# lock_in.net
KiCad netlist of a schematic drawn in Altium Designer
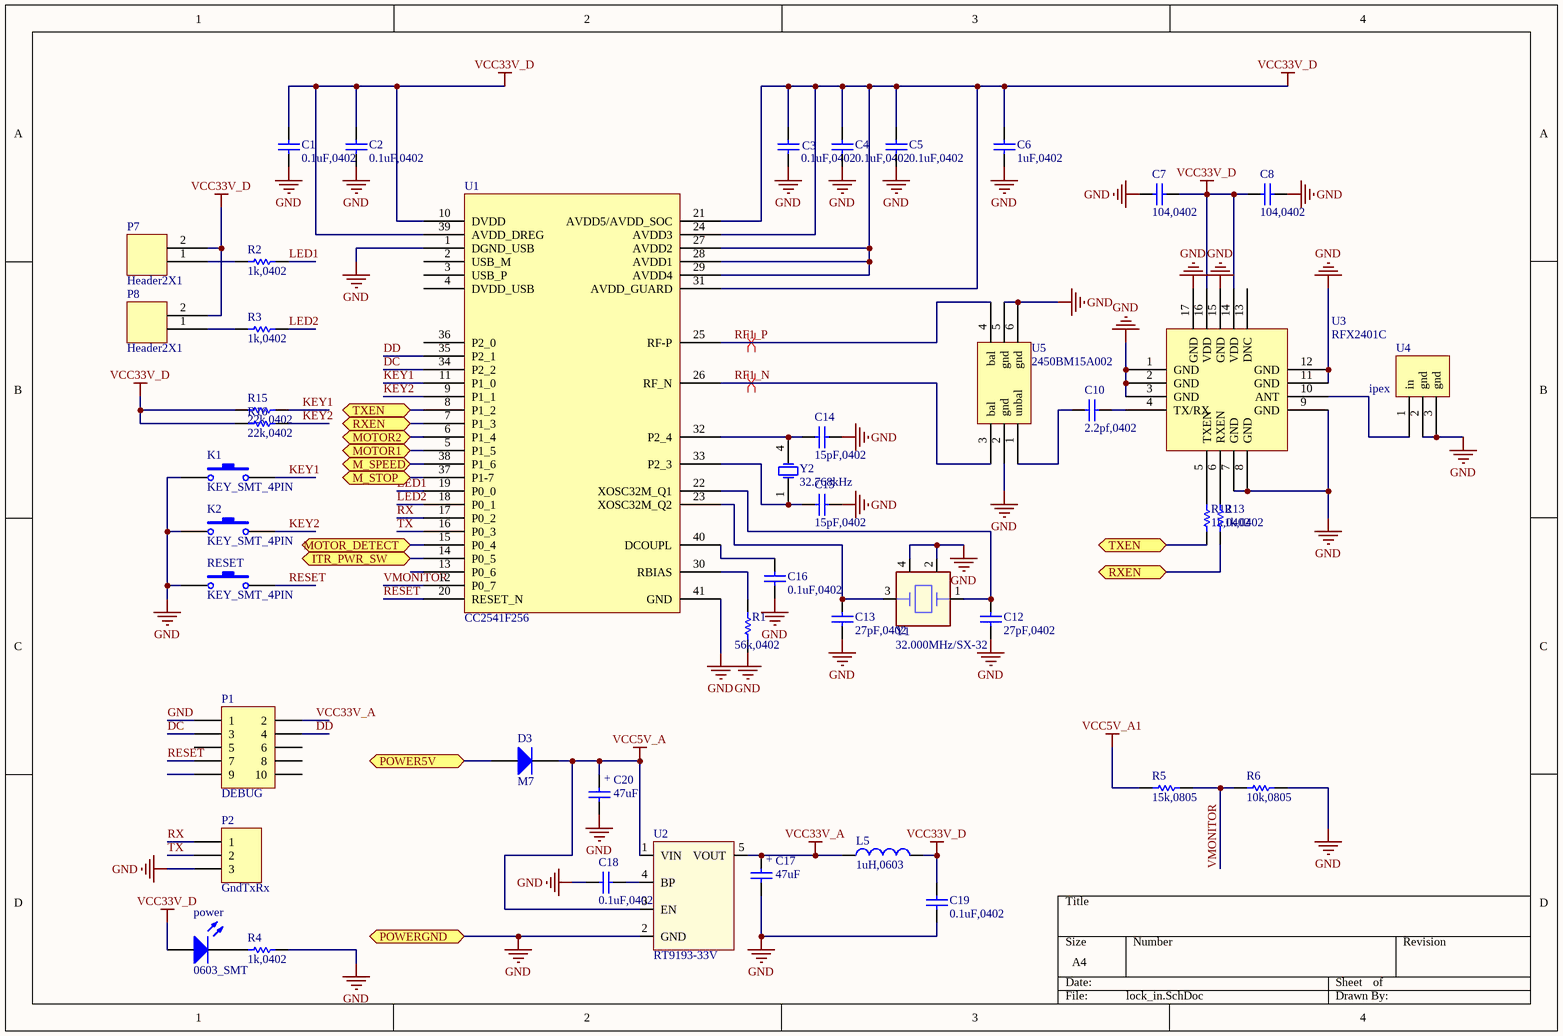
[diagram p0: lock_in.SchDoc]

(export (version "E")
  (design (tool "Eeschema 10.0.6"))
  (components
    (comp (ref "C1")
      (value "0.1uF,0402")
      (footprint "C0402")
      (description "Capacitor")
      (fields (field (name "PUBLISHER") "Altium Limited"))
      (libsource (lib "Inte") (part "CAP"))
    )
    (comp (ref "C2")
      (value "0.1uF,0402")
      (footprint "C0402")
      (description "Capacitor")
      (fields (field (name "PUBLISHER") "Altium Limited"))
      (libsource (lib "Inte") (part "CAP"))
    )
    (comp (ref "C3")
      (value "0.1uF,0402")
      (footprint "C0402")
      (description "Capacitor")
      (fields (field (name "PUBLISHER") "Altium Limited"))
      (libsource (lib "Inte") (part "CAP"))
    )
    (comp (ref "C4")
      (value "0.1uF,0402")
      (footprint "C0402")
      (description "Capacitor")
      (fields (field (name "PUBLISHER") "Altium Limited"))
      (libsource (lib "Inte") (part "CAP"))
    )
    (comp (ref "C5")
      (value "0.1uF,0402")
      (footprint "C0402")
      (description "Capacitor")
      (fields (field (name "PUBLISHER") "Altium Limited"))
      (libsource (lib "Inte") (part "CAP"))
    )
    (comp (ref "C6")
      (value "1uF,0402")
      (footprint "C0402")
      (description "Capacitor")
      (fields (field (name "PUBLISHER") "Altium Limited"))
      (libsource (lib "Inte") (part "CAP"))
    )
    (comp (ref "C7")
      (value "104,0402")
      (footprint "C0402")
      (description "Capacitor")
      (fields (field (name "PUBLISHER") "Altium Limited"))
      (libsource (lib "Inte") (part "CAP"))
    )
    (comp (ref "C8")
      (value "104,0402")
      (footprint "C0402")
      (description "Capacitor")
      (fields (field (name "PUBLISHER") "Altium Limited"))
      (libsource (lib "Inte") (part "CAP"))
    )
    (comp (ref "C10")
      (value "2.2pf,0402")
      (footprint "C0402")
      (description "Capacitor")
      (fields (field (name "PUBLISHER") "Altium Limited"))
      (libsource (lib "Inte") (part "CAP"))
    )
    (comp (ref "C12")
      (value "27pF,0402")
      (footprint "C0402")
      (description "Capacitor")
      (fields (field (name "PUBLISHER") "Altium Limited"))
      (libsource (lib "Inte") (part "CAP"))
    )
    (comp (ref "C13")
      (value "27pF,0402")
      (footprint "C0402")
      (description "Capacitor")
      (fields (field (name "PUBLISHER") "Altium Limited"))
      (libsource (lib "Inte") (part "CAP"))
    )
    (comp (ref "C14")
      (value "15pF,0402")
      (footprint "C0402")
      (description "Capacitor")
      (fields (field (name "PUBLISHER") "Altium Limited"))
      (libsource (lib "Inte") (part "CAP"))
    )
    (comp (ref "C15")
      (value "15pF,0402")
      (footprint "C0402")
      (description "Capacitor")
      (fields (field (name "PUBLISHER") "Altium Limited"))
      (libsource (lib "Inte") (part "CAP"))
    )
    (comp (ref "C16")
      (value "0.1uF,0402")
      (footprint "C0402")
      (description "Capacitor")
      (fields (field (name "PUBLISHER") "Altium Limited"))
      (libsource (lib "Inte") (part "CAP"))
    )
    (comp (ref "C17")
      (value "47uF")
      (footprint "3216")
      (description "tantalum capacitor")
      (libsource (lib "Inte") (part "E_CAP"))
    )
    (comp (ref "C18")
      (value "0.1uF,0402")
      (footprint "C0402")
      (description "Capacitor")
      (fields (field (name "PUBLISHER") "Altium Limited"))
      (libsource (lib "Inte") (part "CAP"))
    )
    (comp (ref "C19")
      (value "0.1uF,0402")
      (footprint "C0402")
      (description "Capacitor")
      (fields (field (name "PUBLISHER") "Altium Limited"))
      (libsource (lib "Inte") (part "CAP"))
    )
    (comp (ref "C20")
      (value "47uF")
      (footprint "3216")
      (description "tantalum capacitor")
      (libsource (lib "Inte") (part "E_CAP"))
    )
    (comp (ref "D3")
      (value "M7")
      (footprint "DO214AC")
      (description "diode")
      (libsource (lib "Inte") (part "DIODE"))
    )
    (comp (ref "K1")
      (value "KEY_SMT_4PIN")
      (footprint "KEY-SMT")
      (description "key")
      (libsource (lib "Inte") (part "KEY"))
    )
    (comp (ref "K2")
      (value "KEY_SMT_4PIN")
      (footprint "KEY-SMT")
      (description "key")
      (libsource (lib "Inte") (part "KEY"))
    )
    (comp (ref "L5")
      (value "1uH,0603")
      (footprint "L0603")
      (description "Inductor")
      (fields (field (name "PUBLISHER") "Altium Limited"))
      (libsource (lib "Inte") (part "Inductor"))
    )
    (comp (ref "P1")
      (value "DEBUG")
      (footprint "HDR2X5")
      (description "Header, 5-Pin, Dual row")
      (fields (field (name "PUBLISHER") "Altium Limited"))
      (libsource (lib "Inte") (part "Header 5X2"))
    )
    (comp (ref "P2")
      (value "GndTxRx")
      (footprint "HDR1X3")
      (description "Header, 3-Pin")
      (fields (field (name "PUBLISHER") "Altium Limited"))
      (libsource (lib "Miscellaneous Connectors") (part "Header 3"))
    )
    (comp (ref "P7")
      (value "Header2X1")
      (footprint "HDR2X1")
      (description "Header,2-Pin")
      (libsource (lib "Inte") (part "Header 2X1"))
    )
    (comp (ref "P8")
      (value "Header2X1")
      (footprint "HDR2X1")
      (description "Header,2-Pin")
      (libsource (lib "Inte") (part "Header 2X1"))
    )
    (comp (ref "power")
      (value "0603_SMT")
      (footprint "LED0603")
      (description "led")
      (libsource (lib "Inte") (part "LED"))
    )
    (comp (ref "R1")
      (value "56k,0402")
      (footprint "R0402")
      (description "Resistor")
      (fields (field (name "PUBLISHER") "Altium Limited"))
      (libsource (lib "Inte") (part "Res1"))
    )
    (comp (ref "R2")
      (value "1k,0402")
      (footprint "R0402")
      (description "Resistor")
      (fields (field (name "PUBLISHER") "Altium Limited"))
      (libsource (lib "Inte") (part "Res1"))
    )
    (comp (ref "R3")
      (value "1k,0402")
      (footprint "R0402")
      (description "Resistor")
      (fields (field (name "PUBLISHER") "Altium Limited"))
      (libsource (lib "Inte") (part "Res1"))
    )
    (comp (ref "R4")
      (value "1k,0402")
      (footprint "R0402")
      (description "Resistor")
      (fields (field (name "PUBLISHER") "Altium Limited"))
      (libsource (lib "Inte") (part "Res1"))
    )
    (comp (ref "R5")
      (value "15k,0805")
      (footprint "R0805")
      (description "Resistor")
      (fields (field (name "PUBLISHER") "Altium Limited"))
      (libsource (lib "Inte") (part "Res1"))
    )
    (comp (ref "R6")
      (value "10k,0805")
      (footprint "R0805")
      (description "Resistor")
      (fields (field (name "PUBLISHER") "Altium Limited"))
      (libsource (lib "Inte") (part "Res1"))
    )
    (comp (ref "R12")
      (value "1k,0402")
      (footprint "R0402")
      (description "Resistor")
      (fields (field (name "PUBLISHER") "Altium Limited"))
      (libsource (lib "Inte") (part "Res1"))
    )
    (comp (ref "R13")
      (value "1k,0402")
      (footprint "R0402")
      (description "Resistor")
      (fields (field (name "PUBLISHER") "Altium Limited"))
      (libsource (lib "Inte") (part "Res1"))
    )
    (comp (ref "R15")
      (value "22k,0402")
      (footprint "R0402")
      (description "Resistor")
      (fields (field (name "PUBLISHER") "Altium Limited"))
      (libsource (lib "Inte") (part "Res1"))
    )
    (comp (ref "R16")
      (value "22k,0402")
      (footprint "R0402")
      (description "Resistor")
      (fields (field (name "PUBLISHER") "Altium Limited"))
      (libsource (lib "Inte") (part "Res1"))
    )
    (comp (ref "RESET")
      (value "KEY_SMT_4PIN")
      (footprint "KEY-SMT")
      (description "key")
      (libsource (lib "Inte") (part "KEY"))
    )
    (comp (ref "U1")
      (value "CC2541F256")
      (footprint "PQFP40")
      (description "TI cc2541F256")
      (libsource (lib "Inte") (part "CC254x"))
    )
    (comp (ref "U2")
      (value "RT9193-33V")
      (footprint "SOT-23-5")
      (description "voltage reg")
      (libsource (lib "Inte") (part "RT9193X"))
    )
    (comp (ref "U3") (value "RFX2401C") (footprint "QFN16") (libsource (lib "Inte") (part "RFX2401C")))
    (comp (ref "U4") (value "ipex") (footprint "IPEX") (libsource (lib "Inte") (part "IPEX")))
    (comp (ref "U5")
      (value "2450BM15A002")
      (footprint "2450BM15A002")
      (libsource (lib "Inte") (part "2450BM15A002"))
    )
    (comp (ref "Y1")
      (value "32.000MHz/SX-32")
      (footprint "1210")
      (description "SPXO")
      (libsource (lib "Inte") (part "CRYSTAL_5"))
    )
    (comp (ref "Y2")
      (value "32.768kHz")
      (footprint "1206")
      (description "crystal")
      (libsource (lib "Inte") (part "DA740C"))
    )
  )
  (nets
    (net (code "1") (name "/DC") (class "Default")
      (node (ref "P1") (pin "3") (pinfunction "3_3") (pintype "passive"))
      (node (ref "U1") (pin "34") (pinfunction "P2_2_34") (pintype "passive"))
    )
    (net (code "2") (name "/DD") (class "Default")
      (node (ref "P1") (pin "4") (pinfunction "4_4") (pintype "passive"))
      (node (ref "U1") (pin "35") (pinfunction "P2_1_35") (pintype "passive"))
    )
    (net (code "3") (name "/ITR_PWR_SW") (class "Default")
      (node (ref "U1") (pin "14") (pinfunction "P0_5_14") (pintype "passive"))
    )
    (net (code "4") (name "/KEY1") (class "Default")
      (node (ref "K1") (pin "2") (pinfunction "2_2") (pintype "passive"))
      (node (ref "R15") (pin "2") (pinfunction "2_2") (pintype "passive"))
      (node (ref "U1") (pin "11") (pinfunction "P1_0_11") (pintype "passive"))
    )
    (net (code "5") (name "/KEY2") (class "Default")
      (node (ref "K2") (pin "2") (pinfunction "2_2") (pintype "passive"))
      (node (ref "R16") (pin "2") (pinfunction "2_2") (pintype "passive"))
      (node (ref "U1") (pin "9") (pinfunction "P1_1_9") (pintype "passive"))
    )
    (net (code "6") (name "/LED1") (class "Default")
      (node (ref "R2") (pin "2") (pinfunction "2_2") (pintype "passive"))
      (node (ref "U1") (pin "19") (pinfunction "P0_0_19") (pintype "passive"))
    )
    (net (code "7") (name "/LED2") (class "Default")
      (node (ref "R3") (pin "2") (pinfunction "2_2") (pintype "passive"))
      (node (ref "U1") (pin "18") (pinfunction "P0_1_18") (pintype "passive"))
    )
    (net (code "8") (name "/MOTOR1") (class "Default")
      (node (ref "U1") (pin "5") (pinfunction "P1_5_5") (pintype "passive"))
    )
    (net (code "9") (name "/MOTOR2") (class "Default")
      (node (ref "U1") (pin "6") (pinfunction "P1_4_6") (pintype "passive"))
    )
    (net (code "10") (name "/MOTOR_DETECT") (class "Default")
      (node (ref "U1") (pin "15") (pinfunction "P0_4_15") (pintype "passive"))
    )
    (net (code "11") (name "/M_SPEED") (class "Default")
      (node (ref "U1") (pin "38") (pinfunction "P1_6_38") (pintype "passive"))
    )
    (net (code "12") (name "/M_STOP") (class "Default")
      (node (ref "U1") (pin "37") (pinfunction "P1-7_37") (pintype "passive"))
    )
    (net (code "13") (name "/POWER5V") (class "Default")
      (node (ref "D3") (pin "1") (pinfunction "A_1") (pintype "passive"))
    )
    (net (code "14") (name "/RESET") (class "Default")
      (node (ref "P1") (pin "7") (pinfunction "7_7") (pintype "passive"))
      (node (ref "RESET") (pin "2") (pinfunction "2_2") (pintype "passive"))
      (node (ref "U1") (pin "20") (pinfunction "RESET_N_20") (pintype "passive"))
    )
    (net (code "15") (name "/RF1_N") (class "Default")
      (node (ref "U1") (pin "26") (pinfunction "RF_N_26") (pintype "passive"))
      (node (ref "U5") (pin "3") (pinfunction "bal_3") (pintype "passive"))
    )
    (net (code "16") (name "/RF1_P") (class "Default")
      (node (ref "U1") (pin "25") (pinfunction "RF-P_25") (pintype "passive"))
      (node (ref "U5") (pin "4") (pinfunction "bal_4") (pintype "passive"))
    )
    (net (code "17") (name "/RX") (class "Default")
      (node (ref "P2") (pin "1") (pinfunction "1_1") (pintype "passive"))
      (node (ref "U1") (pin "17") (pinfunction "P0_2_17") (pintype "passive"))
    )
    (net (code "18") (name "/RXEN") (class "Default")
      (node (ref "R13") (pin "1") (pinfunction "1_1") (pintype "passive"))
      (node (ref "U1") (pin "7") (pinfunction "P1_3_7") (pintype "passive"))
    )
    (net (code "19") (name "/TX") (class "Default")
      (node (ref "P2") (pin "2") (pinfunction "2_2") (pintype "passive"))
      (node (ref "U1") (pin "16") (pinfunction "P0_3_16") (pintype "passive"))
    )
    (net (code "20") (name "/TXEN") (class "Default")
      (node (ref "R12") (pin "1") (pinfunction "1_1") (pintype "passive"))
      (node (ref "U1") (pin "8") (pinfunction "P1_2_8") (pintype "passive"))
    )
    (net (code "21") (name "/VMONITOR") (class "Default")
      (node (ref "R5") (pin "2") (pinfunction "2_2") (pintype "passive"))
      (node (ref "R6") (pin "1") (pinfunction "1_1") (pintype "passive"))
      (node (ref "U1") (pin "12") (pinfunction "P0_7_12") (pintype "passive"))
    )
    (net (code "22") (name "GND") (class "Default")
      (node (ref "C1") (pin "1") (pinfunction "1_1") (pintype "passive"))
      (node (ref "C12") (pin "1") (pinfunction "1_1") (pintype "passive"))
      (node (ref "C13") (pin "1") (pinfunction "1_1") (pintype "passive"))
      (node (ref "C14") (pin "2") (pinfunction "2_2") (pintype "passive"))
      (node (ref "C15") (pin "2") (pinfunction "2_2") (pintype "passive"))
      (node (ref "C16") (pin "1") (pinfunction "1_1") (pintype "passive"))
      (node (ref "C17") (pin "2") (pinfunction "2_2") (pintype "passive"))
      (node (ref "C18") (pin "1") (pinfunction "1_1") (pintype "passive"))
      (node (ref "C19") (pin "1") (pinfunction "1_1") (pintype "passive"))
      (node (ref "C2") (pin "1") (pinfunction "1_1") (pintype "passive"))
      (node (ref "C20") (pin "2") (pinfunction "2_2") (pintype "passive"))
      (node (ref "C3") (pin "2") (pinfunction "2_2") (pintype "passive"))
      (node (ref "C4") (pin "1") (pinfunction "1_1") (pintype "passive"))
      (node (ref "C5") (pin "1") (pinfunction "1_1") (pintype "passive"))
      (node (ref "C6") (pin "1") (pinfunction "1_1") (pintype "passive"))
      (node (ref "C7") (pin "1") (pinfunction "1_1") (pintype "passive"))
      (node (ref "C8") (pin "2") (pinfunction "2_2") (pintype "passive"))
      (node (ref "K1") (pin "1") (pinfunction "1_1") (pintype "passive"))
      (node (ref "K2") (pin "1") (pinfunction "1_1") (pintype "passive"))
      (node (ref "P1") (pin "1") (pinfunction "1_1") (pintype "passive"))
      (node (ref "P2") (pin "3") (pinfunction "3_3") (pintype "passive"))
      (node (ref "R1") (pin "1") (pinfunction "1_1") (pintype "passive"))
      (node (ref "R4") (pin "2") (pinfunction "2_2") (pintype "passive"))
      (node (ref "R6") (pin "2") (pinfunction "2_2") (pintype "passive"))
      (node (ref "RESET") (pin "1") (pinfunction "1_1") (pintype "passive"))
      (node (ref "U1") (pin "1") (pinfunction "DGND_USB_1") (pintype "passive"))
      (node (ref "U1") (pin "41") (pinfunction "GND_41") (pintype "passive"))
      (node (ref "U2") (pin "2") (pinfunction "GND_2") (pintype "power_in"))
      (node (ref "U3") (pin "1") (pinfunction "GND_1") (pintype "passive"))
      (node (ref "U3") (pin "11") (pinfunction "GND_11") (pintype "passive"))
      (node (ref "U3") (pin "12") (pinfunction "GND_12") (pintype "passive"))
      (node (ref "U3") (pin "15") (pinfunction "GND_15") (pintype "passive"))
      (node (ref "U3") (pin "17") (pinfunction "GND_17") (pintype "passive"))
      (node (ref "U3") (pin "2") (pinfunction "GND_2") (pintype "passive"))
      (node (ref "U3") (pin "3") (pinfunction "GND_3") (pintype "passive"))
      (node (ref "U3") (pin "7") (pinfunction "GND_7") (pintype "passive"))
      (node (ref "U3") (pin "8") (pinfunction "GND_8") (pintype "passive"))
      (node (ref "U3") (pin "9") (pinfunction "GND_9") (pintype "passive"))
      (node (ref "U4") (pin "2") (pinfunction "gnd_2") (pintype "passive"))
      (node (ref "U4") (pin "3") (pinfunction "gnd_3") (pintype "passive"))
      (node (ref "U5") (pin "2") (pinfunction "gnd_2") (pintype "passive"))
      (node (ref "U5") (pin "5") (pinfunction "gnd_5") (pintype "passive"))
      (node (ref "U5") (pin "6") (pinfunction "gnd_6") (pintype "passive"))
      (node (ref "Y1") (pin "2") (pinfunction "2_2") (pintype "passive"))
      (node (ref "Y1") (pin "4") (pinfunction "4_4") (pintype "passive"))
    )
    (net (code "23") (name "Net-(P7-Pad1)") (class "Default")
      (node (ref "P7") (pin "1") (pinfunction "1_1") (pintype "passive"))
      (node (ref "R2") (pin "1") (pinfunction "1_1") (pintype "passive"))
    )
    (net (code "24") (name "Net-(P8-Pad1)") (class "Default")
      (node (ref "P8") (pin "1") (pinfunction "1_1") (pintype "passive"))
      (node (ref "R3") (pin "1") (pinfunction "1_1") (pintype "passive"))
    )
    (net (code "25") (name "Net-(U1-DCOUPL)") (class "Default")
      (node (ref "C16") (pin "2") (pinfunction "2_2") (pintype "passive"))
      (node (ref "U1") (pin "40") (pinfunction "DCOUPL_40") (pintype "passive"))
    )
    (net (code "26") (name "Net-(U1-P2_3)") (class "Default")
      (node (ref "C15") (pin "1") (pinfunction "1_1") (pintype "passive"))
      (node (ref "U1") (pin "33") (pinfunction "P2_3_33") (pintype "passive"))
      (node (ref "Y2") (pin "1") (pinfunction "OSC1_1") (pintype "passive"))
    )
    (net (code "27") (name "Net-(U1-P2_4)") (class "Default")
      (node (ref "C14") (pin "1") (pinfunction "1_1") (pintype "passive"))
      (node (ref "U1") (pin "32") (pinfunction "P2_4_32") (pintype "passive"))
      (node (ref "Y2") (pin "4") (pinfunction "OSC2_4") (pintype "passive"))
    )
    (net (code "28") (name "Net-(U1-RBIAS)") (class "Default")
      (node (ref "R1") (pin "2") (pinfunction "2_2") (pintype "passive"))
      (node (ref "U1") (pin "30") (pinfunction "RBIAS_30") (pintype "passive"))
    )
    (net (code "29") (name "Net-(U1-XOSC32M_Q1)") (class "Default")
      (node (ref "C12") (pin "2") (pinfunction "2_2") (pintype "passive"))
      (node (ref "U1") (pin "22") (pinfunction "XOSC32M_Q1_22") (pintype "passive"))
      (node (ref "Y1") (pin "1") (pinfunction "1_1") (pintype "passive"))
    )
    (net (code "30") (name "Net-(U1-XOSC32M_Q2)") (class "Default")
      (node (ref "C13") (pin "2") (pinfunction "2_2") (pintype "passive"))
      (node (ref "U1") (pin "23") (pinfunction "XOSC32M_Q2_23") (pintype "passive"))
      (node (ref "Y1") (pin "3") (pinfunction "3_3") (pintype "passive"))
    )
    (net (code "31") (name "Net-(U2-BP)") (class "Default")
      (node (ref "C18") (pin "2") (pinfunction "2_2") (pintype "passive"))
      (node (ref "U2") (pin "4") (pinfunction "BP_4") (pintype "passive"))
    )
    (net (code "32") (name "Net-(U3-ANT)") (class "Default")
      (node (ref "U3") (pin "10") (pinfunction "ANT_10") (pintype "passive"))
      (node (ref "U4") (pin "1") (pinfunction "in_1") (pintype "passive"))
    )
    (net (code "33") (name "Net-(U3-RXEN)") (class "Default")
      (node (ref "R13") (pin "2") (pinfunction "2_2") (pintype "passive"))
      (node (ref "U3") (pin "6") (pinfunction "RXEN_6") (pintype "passive"))
    )
    (net (code "34") (name "Net-(U3-TXEN)") (class "Default")
      (node (ref "R12") (pin "2") (pinfunction "2_2") (pintype "passive"))
      (node (ref "U3") (pin "5") (pinfunction "TXEN_5") (pintype "passive"))
    )
    (net (code "35") (name "Net-(U3-TX{slash}RX)") (class "Default")
      (node (ref "C10") (pin "2") (pinfunction "2_2") (pintype "passive"))
      (node (ref "U3") (pin "4") (pinfunction "TX/RX_4") (pintype "passive"))
    )
    (net (code "36") (name "Net-(U5-unbal)") (class "Default")
      (node (ref "C10") (pin "1") (pinfunction "1_1") (pintype "passive"))
      (node (ref "U5") (pin "1") (pinfunction "unbal_1") (pintype "passive"))
    )
    (net (code "37") (name "Net-(power-K)") (class "Default")
      (node (ref "R4") (pin "1") (pinfunction "1_1") (pintype "passive"))
      (node (ref "power") (pin "2") (pinfunction "K_2") (pintype "passive"))
    )
    (net (code "38") (name "VCC5V_A") (class "Default")
      (node (ref "C20") (pin "1") (pinfunction "1_1") (pintype "passive"))
      (node (ref "D3") (pin "2") (pinfunction "K_2") (pintype "passive"))
      (node (ref "U2") (pin "1") (pinfunction "VIN_1") (pintype "power_in"))
      (node (ref "U2") (pin "3") (pinfunction "EN_3") (pintype "passive"))
    )
    (net (code "39") (name "VCC5V_A1") (class "Default")
      (node (ref "R5") (pin "1") (pinfunction "1_1") (pintype "passive"))
    )
    (net (code "40") (name "VCC33V_A") (class "Default")
      (node (ref "C17") (pin "1") (pinfunction "1_1") (pintype "passive"))
      (node (ref "L5") (pin "1") (pinfunction "1_1") (pintype "passive"))
      (node (ref "P1") (pin "2") (pinfunction "2_2") (pintype "passive"))
      (node (ref "U2") (pin "5") (pinfunction "VOUT_5") (pintype "power_in"))
    )
    (net (code "41") (name "VCC33V_D") (class "Default")
      (node (ref "C1") (pin "2") (pinfunction "2_2") (pintype "passive"))
      (node (ref "C19") (pin "2") (pinfunction "2_2") (pintype "passive"))
      (node (ref "C2") (pin "2") (pinfunction "2_2") (pintype "passive"))
      (node (ref "C3") (pin "1") (pinfunction "1_1") (pintype "passive"))
      (node (ref "C4") (pin "2") (pinfunction "2_2") (pintype "passive"))
      (node (ref "C5") (pin "2") (pinfunction "2_2") (pintype "passive"))
      (node (ref "C6") (pin "2") (pinfunction "2_2") (pintype "passive"))
      (node (ref "C7") (pin "2") (pinfunction "2_2") (pintype "passive"))
      (node (ref "C8") (pin "1") (pinfunction "1_1") (pintype "passive"))
      (node (ref "L5") (pin "2") (pinfunction "2_2") (pintype "passive"))
      (node (ref "P7") (pin "2") (pinfunction "2_2") (pintype "passive"))
      (node (ref "P8") (pin "2") (pinfunction "2_2") (pintype "passive"))
      (node (ref "R15") (pin "1") (pinfunction "1_1") (pintype "passive"))
      (node (ref "R16") (pin "1") (pinfunction "1_1") (pintype "passive"))
      (node (ref "U1") (pin "10") (pinfunction "DVDD_10") (pintype "passive"))
      (node (ref "U1") (pin "21") (pinfunction "AVDD5/AVDD_SOC_21") (pintype "passive"))
      (node (ref "U1") (pin "24") (pinfunction "AVDD3_24") (pintype "passive"))
      (node (ref "U1") (pin "27") (pinfunction "AVDD2_27") (pintype "passive"))
      (node (ref "U1") (pin "28") (pinfunction "AVDD1_28") (pintype "passive"))
      (node (ref "U1") (pin "29") (pinfunction "AVDD4_29") (pintype "passive"))
      (node (ref "U1") (pin "31") (pinfunction "AVDD_GUARD_31") (pintype "passive"))
      (node (ref "U1") (pin "39") (pinfunction "AVDD_DREG_39") (pintype "passive"))
      (node (ref "U3") (pin "14") (pinfunction "VDD_14") (pintype "passive"))
      (node (ref "U3") (pin "16") (pinfunction "VDD_16") (pintype "passive"))
      (node (ref "power") (pin "1") (pinfunction "A_1") (pintype "passive"))
    )
    (net (code "42") (name "unconnected-(P1-Pad5)") (class "Default")
      (node (ref "P1") (pin "5") (pinfunction "5_5") (pintype "passive"))
    )
    (net (code "43") (name "unconnected-(P1-Pad6)") (class "Default")
      (node (ref "P1") (pin "6") (pinfunction "6_6") (pintype "passive"))
    )
    (net (code "44") (name "unconnected-(P1-Pad8)") (class "Default")
      (node (ref "P1") (pin "8") (pinfunction "8_8") (pintype "passive"))
    )
    (net (code "45") (name "unconnected-(P1-Pad9)") (class "Default")
      (node (ref "P1") (pin "9") (pinfunction "9_9") (pintype "passive"))
    )
    (net (code "46") (name "unconnected-(P1-Pad10)") (class "Default")
      (node (ref "P1") (pin "10") (pinfunction "10_10") (pintype "passive"))
    )
    (net (code "47") (name "unconnected-(U1-DVDD_USB-Pad4)") (class "Default")
      (node (ref "U1") (pin "4") (pinfunction "DVDD_USB_4") (pintype "passive"))
    )
    (net (code "48") (name "unconnected-(U1-P0_6-Pad13)") (class "Default")
      (node (ref "U1") (pin "13") (pinfunction "P0_6_13") (pintype "passive"))
    )
    (net (code "49") (name "unconnected-(U1-P2_0-Pad36)") (class "Default")
      (node (ref "U1") (pin "36") (pinfunction "P2_0_36") (pintype "passive"))
    )
    (net (code "50") (name "unconnected-(U1-USB_M-Pad2)") (class "Default")
      (node (ref "U1") (pin "2") (pinfunction "USB_M_2") (pintype "passive"))
    )
    (net (code "51") (name "unconnected-(U1-USB_P-Pad3)") (class "Default")
      (node (ref "U1") (pin "3") (pinfunction "USB_P_3") (pintype "passive"))
    )
    (net (code "52") (name "unconnected-(U3-DNC-Pad13)") (class "Default")
      (node (ref "U3") (pin "13") (pinfunction "DNC_13") (pintype "passive"))
    )
  )
)
